# Constant_Current_Sink.net
KiCad netlist of a schematic drawn in Altium Designer
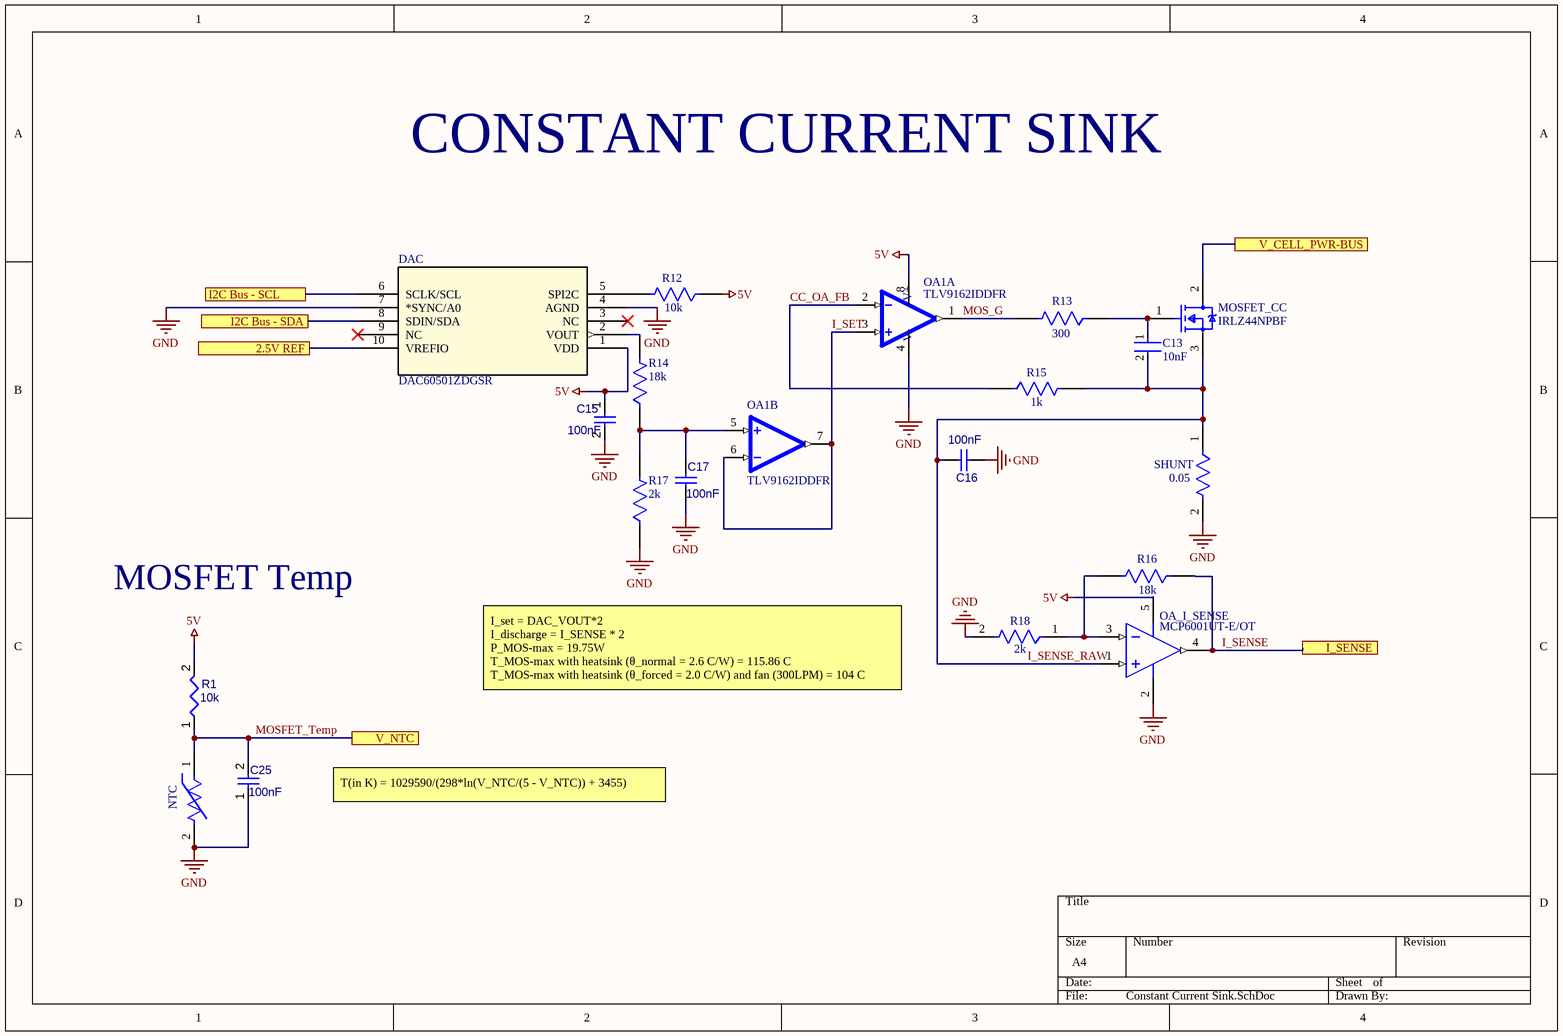
[diagram p0: Constant Current Sink.SchDoc]

(export (version "E")
  (design (tool "Eeschema 10.0.6"))
  (components
    (comp (ref "C13")
      (value "10nF")
      (footprint "FP-GCM219-0_15-IPC_C")
      (description "Ceramic Capacitor for Automotive 10nF  ±10% 100VDC X8R 0805 Paper T/R")
      (libsource (lib "Altium Content Vault") (part "11868f565c42a9108669ba33697ecf6"))
    )
    (comp (ref "C15")
      (value "100nF")
      (footprint "CAPC2013X95X50LL10T25")
      (description "Capacitor 100 nF +/-10% 50 V 0805")
      (fields (field (name "TOLERANCE") "10%"))
      (libsource (lib "") (part "CAP-NP-2_1"))
    )
    (comp (ref "C16")
      (value "100nF")
      (footprint "CAPC2013X95X50LL10T25")
      (description "Capacitor 100 nF +/-10% 50 V 0805")
      (fields (field (name "TOLERANCE") "10%"))
      (libsource (lib "gugan Sivakumar") (part "CAP-NP-2"))
    )
    (comp (ref "C17")
      (value "100nF")
      (footprint "CAPC2013X95X50LL10T25")
      (description "Capacitor 100 nF +/-10% 50 V 0805")
      (fields (field (name "TOLERANCE") "10%"))
      (libsource (lib "gugan Sivakumar") (part "CAP-NP-2"))
    )
    (comp (ref "C25")
      (value "100nF")
      (footprint "CAPC2013X95X50LL10T25")
      (description "Capacitor 100 nF +/-10% 50 V 0805")
      (fields (field (name "TOLERANCE") "10%"))
      (libsource (lib "") (part "CAP-NP-2_1"))
    )
    (comp (ref "DAC")
      (value "DAC60501ZDGSR")
      (footprint "DGS10_TEX")
      (fields (field (name "COPYRIGHT") "Copyright (C) 2025 Ultra Librarian. All rights reserved."))
      (libsource (lib "DAC60501ZDGSR") (part "DAC60501ZDGSR"))
    )
    (comp (ref "MOSFET_CC")
      (value "IRLZ44NPBF")
      (footprint "FP-PG-TO220-3-MFG")
      (description "MOSFET N-CH 55V 47A TO220AB")
      (libsource (lib "Altium Content Vault") (part "b09f7f152735e370c1ea22a33fa83d6"))
    )
    (comp (ref "NTC")
      (value "NXRT15XH103FA1B030")
      (footprint "FP-NXR_151B030-MFG")
      (description "Thermistor NTC 10kΩ ±1% 2-Pin Radial Bulk")
      (fields (field (name "TOLERANCE") "1%"))
      (libsource (lib "Altium Content Vault") (part "3b148a6ebabc5fb4d708a66c052d352"))
    )
    (comp (ref "OA1")
      (value "TLV9162IDDFR")
      (footprint "SOT65P280X110-8N")
      (description "Dual, 16V, 11MHz, rail-to-rail input and output low-offset-voltage low-noise operational amplifier")
      (fields (field (name "MF") "Texas Instruments"))
      (libsource (lib "gugan Sivakumar") (part "TLV9162IDDFR"))
    )
    (comp (ref "OA_I_SENSE")
      (value "MCP6001UT-E/OT")
      (footprint "SOT-23-OT5_L")
      (description "None")
      (libsource (lib "Altium Content Vault") (part "AMP-OPA-MCP6001U-SOT5"))
    )
    (comp (ref "R1")
      (value "10k")
      (footprint "RESC2013X50X35ML15T15")
      (description "Chip Resistor, 10 KOhm, +/- 1%, 125 mW, -55 to 155 degC, 0805 (2012 Metric)")
      (fields (field (name "TOLERANCE") "1%") (field (name "POWER") "125mW"))
      (libsource (lib "gugan Sivakumar") (part "RES-2"))
    )
    (comp (ref "R12")
      (value "10k")
      (footprint "FP-AC0603-IPC_A")
      (description "RES 10kΩ 5.00% 0.2W 0603")
      (libsource (lib "") (part "1029c3af85768c4190bb7ad29bc67b5_1"))
    )
    (comp (ref "R13")
      (value "300")
      (footprint "FP-CR0805-MFG")
      (description "CR0805-FX-3000ELF Thick Film Chip Resistors 0805 300Ω 0.125W 1% 100ppm/°C")
      (fields (field (name "TOLERANCE") "1%"))
      (libsource (lib "") (part "1029c3af85768c4190bb7ad29bc67b5_1"))
    )
    (comp (ref "R14")
      (value "18k")
      (footprint "FP-CRGP0805-IPC_C")
      (description "CRGP0805F18K CRGP0805 18KΩ 0.33W ±100ppm/°C 1% 150V")
      (fields
        (field (name "MANUFACTURER PART NUMBER") "CRGP0805F18K")
        (field (name "OCTOPART") "https://octopart.com/crgp0805f18k-te+connectivity-91018794")
      )
      (libsource (lib "") (part "1029c3af85768c4190bb7ad29bc67b5_1"))
    )
    (comp (ref "R15")
      (value "1k")
      (footprint "FP-RN73R2A-IPC_A")
      (libsource (lib "") (part "1029c3af85768c4190bb7ad29bc67b5_1"))
    )
    (comp (ref "R16")
      (value "18k")
      (footprint "FP-CRGP0805-IPC_C")
      (description "CRGP0805F18K CRGP0805 18KΩ 0.33W ±100ppm/°C 1% 150V")
      (fields
        (field (name "MANUFACTURER PART NUMBER") "CRGP0805F18K")
        (field (name "OCTOPART") "https://octopart.com/crgp0805f18k-te+connectivity-91018794")
      )
      (libsource (lib "") (part "1029c3af85768c4190bb7ad29bc67b5_1"))
    )
    (comp (ref "R17")
      (value "2k")
      (footprint "FP-MCU0805-IPC_A")
      (description "MCU08050D2001BP500 RES 1.05K OHM 0.5% 1/5W 0805")
      (fields (field (name "TOLERANCE") "0.1%"))
      (libsource (lib "") (part "1029c3af85768c4190bb7ad29bc67b5_1"))
    )
    (comp (ref "R18")
      (value "2k")
      (footprint "FP-MCU0805-IPC_A")
      (description "MCU08050D2001BP500 RES 1.05K OHM 0.5% 1/5W 0805")
      (fields (field (name "TOLERANCE") "0.1%"))
      (libsource (lib "Altium Content Vault") (part "1029c3af85768c4190bb7ad29bc67b5"))
    )
    (comp (ref "SHUNT")
      (value "0.05")
      (footprint "FP-CRA2512-IPC_A")
      (description "RES 0.05 OHM 1% 3W 2512")
      (libsource (lib "Altium Content Vault") (part "1029c3af85768c4190bb7ad29bc67b5"))
    )
  )
  (nets
    (net (code "1") (name "/2.5V REF") (class "Default")
      (node (ref "DAC") (pin "10") (pinfunction "VREFIO_10") (pintype "power_in"))
    )
    (net (code "2") (name "/CC_OA_FB") (class "Default")
      (node (ref "OA1") (pin "2") (pinfunction "IN1-_2") (pintype "input"))
      (node (ref "R15") (pin "1") (pinfunction "1_1") (pintype "passive"))
    )
    (net (code "3") (name "/I2C Bus - SCL") (class "Default")
      (node (ref "DAC") (pin "6") (pinfunction "SCLK/SCL_6") (pintype "passive"))
    )
    (net (code "4") (name "/I2C Bus - SDA") (class "Default")
      (node (ref "DAC") (pin "8") (pinfunction "SDIN/SDA_8") (pintype "passive"))
    )
    (net (code "5") (name "/I_SENSE") (class "Default")
      (node (ref "OA_I_SENSE") (pin "4") (pinfunction "VOUT_4") (pintype "output"))
      (node (ref "R16") (pin "1") (pinfunction "1_1") (pintype "passive"))
    )
    (net (code "6") (name "/I_SENSE_RAW") (class "Default")
      (node (ref "C13") (pin "2") (pinfunction "2_2") (pintype "passive"))
      (node (ref "C16") (pin "1") (pinfunction "1_1") (pintype "passive"))
      (node (ref "MOSFET_CC") (pin "3") (pinfunction "S_3") (pintype "passive"))
      (node (ref "OA_I_SENSE") (pin "1") (pinfunction "VIN+_1") (pintype "input"))
      (node (ref "R15") (pin "2") (pinfunction "2_2") (pintype "passive"))
      (node (ref "SHUNT") (pin "1") (pinfunction "1_1") (pintype "passive"))
    )
    (net (code "7") (name "/I_SET") (class "Default")
      (node (ref "OA1") (pin "3") (pinfunction "IN1+_3") (pintype "input"))
      (node (ref "OA1") (pin "6") (pinfunction "IN2-_6") (pintype "input"))
      (node (ref "OA1") (pin "7") (pinfunction "OUT2_7") (pintype "output"))
    )
    (net (code "8") (name "/MOSFET_Temp") (class "Default")
      (node (ref "C25") (pin "2") (pinfunction "2_2") (pintype "passive"))
      (node (ref "NTC") (pin "1") (pinfunction "1_1") (pintype "passive"))
      (node (ref "R1") (pin "1") (pinfunction "1_1") (pintype "passive"))
    )
    (net (code "9") (name "/MOS_G") (class "Default")
      (node (ref "OA1") (pin "1") (pinfunction "OUT1_1") (pintype "output"))
      (node (ref "R13") (pin "2") (pinfunction "2_2") (pintype "passive"))
    )
    (net (code "10") (name "/V_CELL_PWR-BUS") (class "Default")
      (node (ref "MOSFET_CC") (pin "2") (pinfunction "D_2") (pintype "passive"))
    )
    (net (code "11") (name "5V") (class "Default")
      (node (ref "C15") (pin "1") (pinfunction "1_1") (pintype "passive"))
      (node (ref "DAC") (pin "1") (pinfunction "VDD_1") (pintype "power_in"))
      (node (ref "OA1") (pin "8") (pinfunction "V+_8") (pintype "power_in"))
      (node (ref "OA_I_SENSE") (pin "5") (pinfunction "VDD_5") (pintype "power_in"))
      (node (ref "R1") (pin "2") (pinfunction "2_2") (pintype "passive"))
      (node (ref "R12") (pin "1") (pinfunction "1_1") (pintype "passive"))
    )
    (net (code "12") (name "GND") (class "Default")
      (node (ref "C15") (pin "2") (pinfunction "2_2") (pintype "passive"))
      (node (ref "C16") (pin "2") (pinfunction "2_2") (pintype "passive"))
      (node (ref "C17") (pin "2") (pinfunction "2_2") (pintype "passive"))
      (node (ref "C25") (pin "1") (pinfunction "1_1") (pintype "passive"))
      (node (ref "DAC") (pin "4") (pinfunction "AGND_4") (pintype "power_in"))
      (node (ref "DAC") (pin "7") (pinfunction "*SYNC/A0_7") (pintype "passive"))
      (node (ref "NTC") (pin "2") (pinfunction "2_2") (pintype "passive"))
      (node (ref "OA1") (pin "4") (pinfunction "V-_4") (pintype "power_in"))
      (node (ref "OA_I_SENSE") (pin "2") (pinfunction "VSS_2") (pintype "power_in"))
      (node (ref "R17") (pin "1") (pinfunction "1_1") (pintype "passive"))
      (node (ref "R18") (pin "2") (pinfunction "2_2") (pintype "passive"))
      (node (ref "SHUNT") (pin "2") (pinfunction "2_2") (pintype "passive"))
    )
    (net (code "13") (name "Net-(DAC-SPI2C)") (class "Default")
      (node (ref "DAC") (pin "5") (pinfunction "SPI2C_5") (pintype "passive"))
      (node (ref "R12") (pin "2") (pinfunction "2_2") (pintype "passive"))
    )
    (net (code "14") (name "Net-(DAC-VOUT)") (class "Default")
      (node (ref "DAC") (pin "2") (pinfunction "VOUT_2") (pintype "output"))
      (node (ref "R14") (pin "2") (pinfunction "2_2") (pintype "passive"))
    )
    (net (code "15") (name "Net-(MOSFET_CC-G)") (class "Default")
      (node (ref "C13") (pin "1") (pinfunction "1_1") (pintype "passive"))
      (node (ref "MOSFET_CC") (pin "1") (pinfunction "G_1") (pintype "passive"))
      (node (ref "R13") (pin "1") (pinfunction "1_1") (pintype "passive"))
    )
    (net (code "16") (name "Net-(OA1B-IN2+)") (class "Default")
      (node (ref "C17") (pin "1") (pinfunction "1_1") (pintype "passive"))
      (node (ref "OA1") (pin "5") (pinfunction "IN2+_5") (pintype "input"))
      (node (ref "R14") (pin "1") (pinfunction "1_1") (pintype "passive"))
      (node (ref "R17") (pin "2") (pinfunction "2_2") (pintype "passive"))
    )
    (net (code "17") (name "Net-(OA_I_SENSE-VIN-)") (class "Default")
      (node (ref "OA_I_SENSE") (pin "3") (pinfunction "VIN-_3") (pintype "input"))
      (node (ref "R16") (pin "2") (pinfunction "2_2") (pintype "passive"))
      (node (ref "R18") (pin "1") (pinfunction "1_1") (pintype "passive"))
    )
    (net (code "18") (name "unconnected-(DAC-NC-Pad3)") (class "Default")
      (node (ref "DAC") (pin "3") (pinfunction "NC_3") (pintype "passive+no_connect"))
    )
    (net (code "19") (name "unconnected-(DAC-NC-Pad9)") (class "Default")
      (node (ref "DAC") (pin "9") (pinfunction "NC_9") (pintype "passive+no_connect"))
    )
  )
)
